# 10_RK3588_VCCIO1_VCCIO3_SARADC.net
KiCad netlist of a schematic drawn in Altium Designer
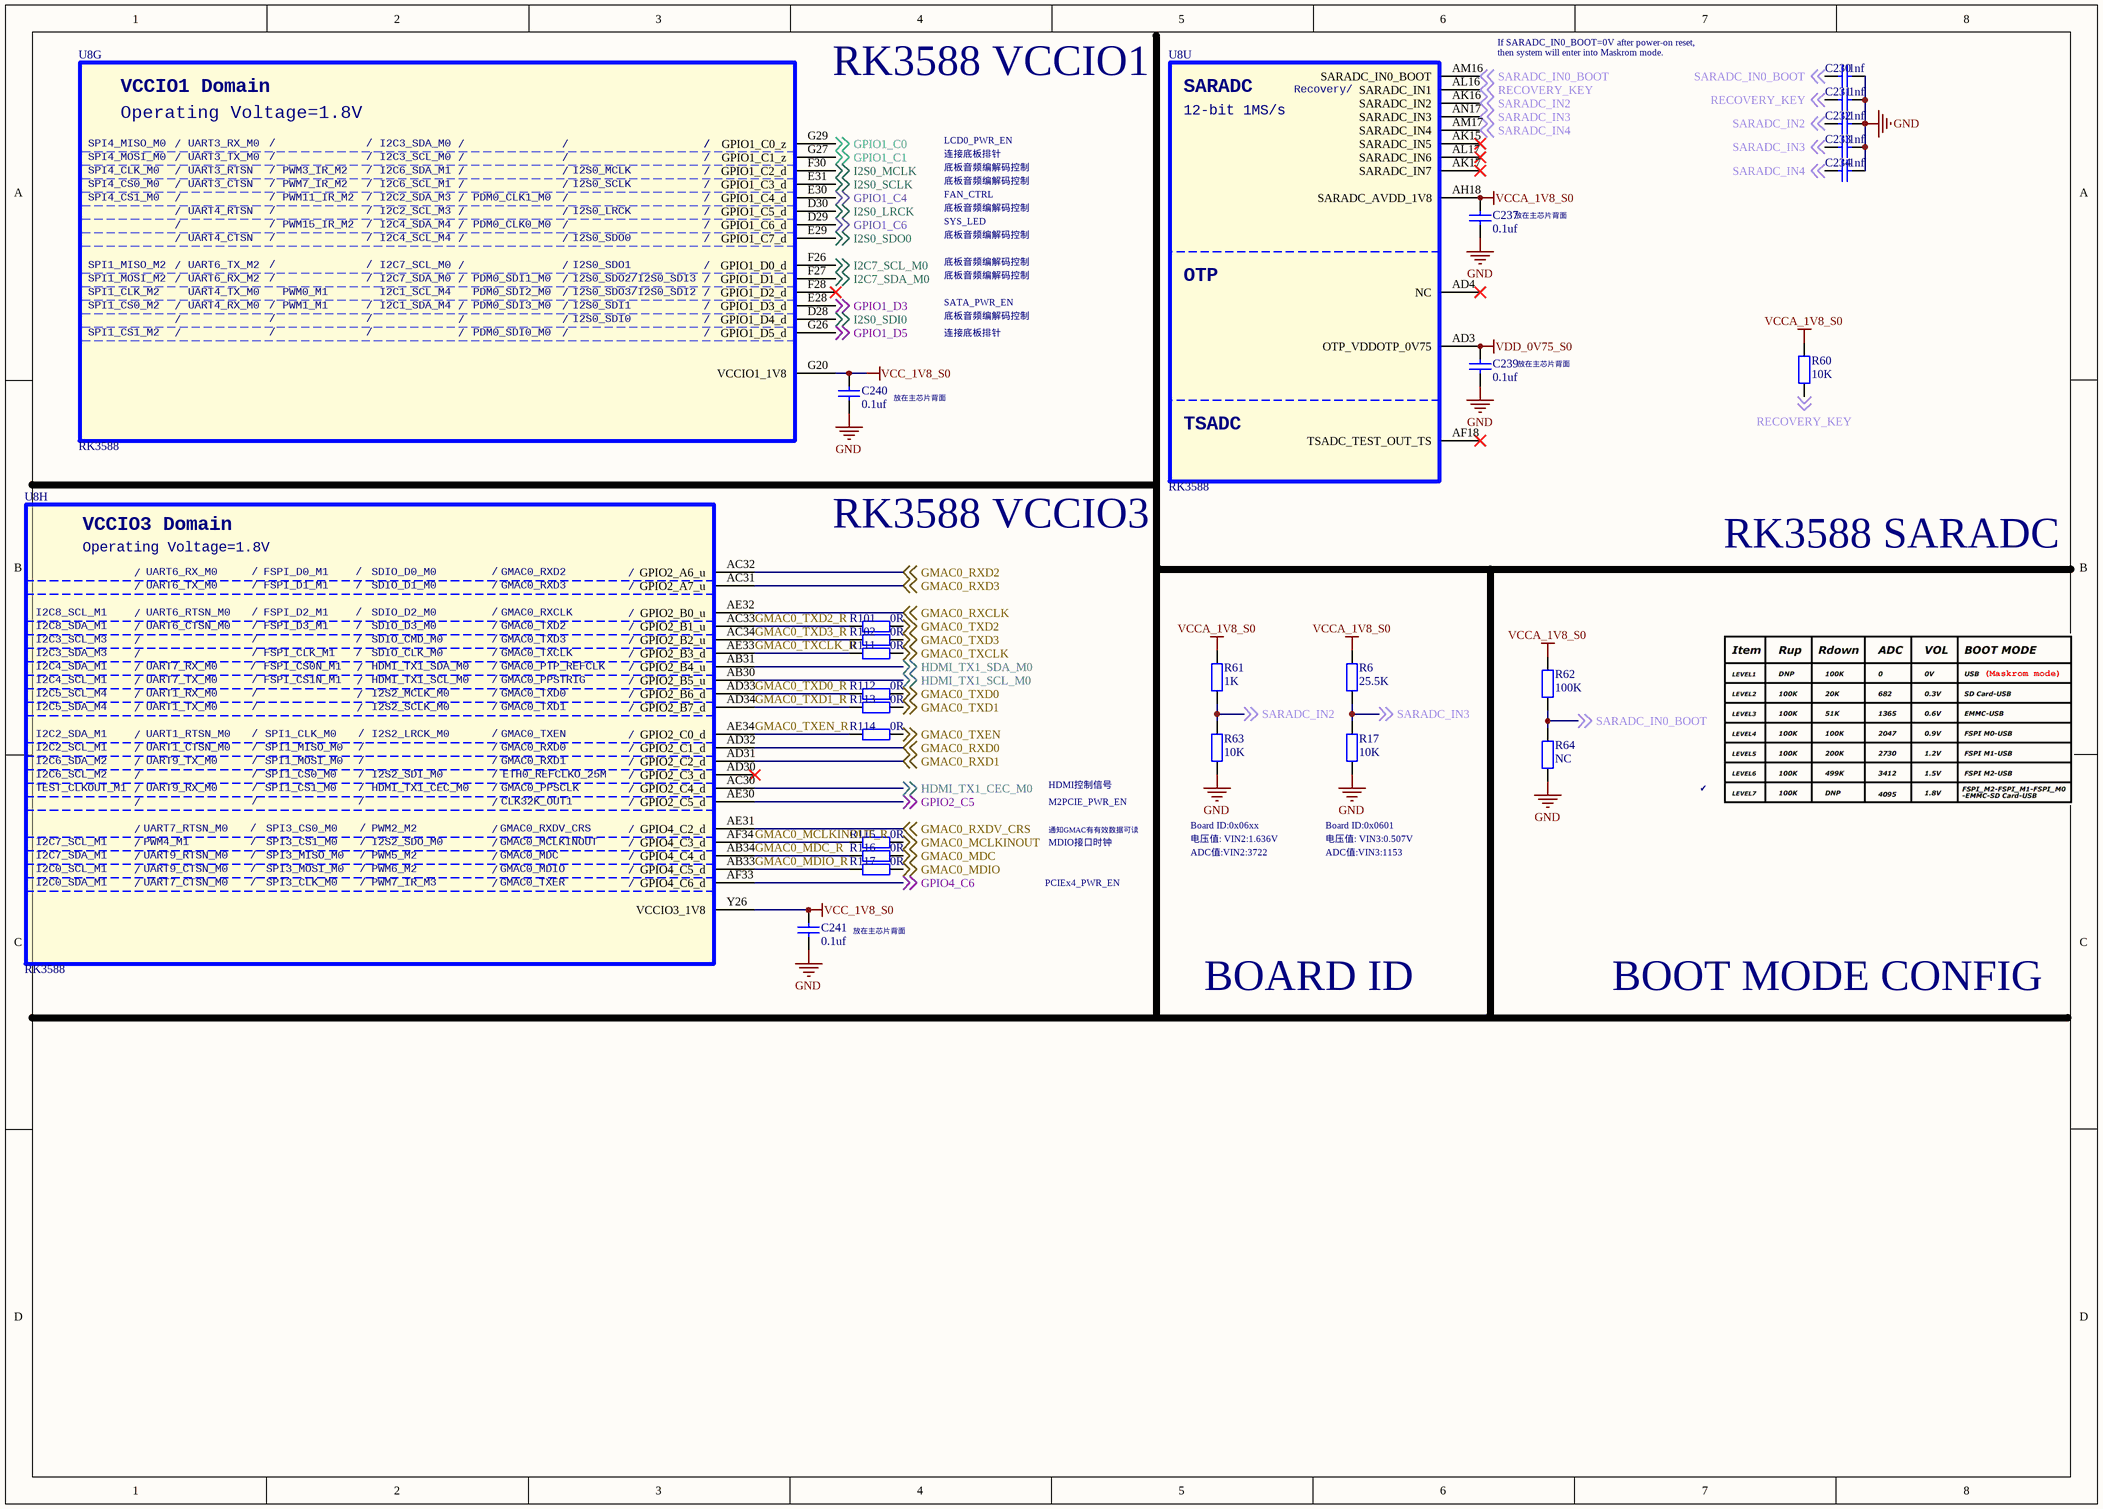
[diagram p0: 10.RK3588_VCCIO1_VCCIO3_SARADC.SchDoc]

(export (version "E")
  (design (tool "Eeschema 10.0.6"))
  (components
    (comp (ref "C230")
      (value "1nf")
      (footprint "0.PCB1:C0201_L")
      (description "贴片电容/MLCC电容")
      (libsource (lib "RK3588") (part "C"))
    )
    (comp (ref "C231")
      (value "1nf")
      (footprint "0.PCB1:C0201_L")
      (description "贴片电容/MLCC电容")
      (libsource (lib "RK3588") (part "C"))
    )
    (comp (ref "C232")
      (value "1nf")
      (footprint "0.PCB1:C0201_L")
      (description "贴片电容/MLCC电容")
      (libsource (lib "RK3588") (part "C"))
    )
    (comp (ref "C233")
      (value "1nf")
      (footprint "0.PCB1:C0201_L")
      (description "贴片电容/MLCC电容")
      (libsource (lib "RK3588") (part "C"))
    )
    (comp (ref "C234")
      (value "1nf")
      (footprint "0.PCB1:C0201_L")
      (description "贴片电容/MLCC电容")
      (libsource (lib "RK3588") (part "C"))
    )
    (comp (ref "C237")
      (value "0.1uf")
      (footprint "0.PCB1:C0201_L")
      (description "贴片电容/MLCC电容")
      (libsource (lib "RK3588") (part "C"))
    )
    (comp (ref "C239")
      (value "0.1uf")
      (footprint "0.PCB1:C0201_L")
      (description "贴片电容/MLCC电容")
      (libsource (lib "RK3588") (part "C"))
    )
    (comp (ref "C240")
      (value "0.1uf")
      (footprint "0.PCB1:C0201_L")
      (description "贴片电容/MLCC电容")
      (libsource (lib "RK3588") (part "C"))
    )
    (comp (ref "C241")
      (value "0.1uf")
      (footprint "0.PCB1:C0201_L")
      (description "贴片电容/MLCC电容")
      (libsource (lib "RK3588") (part "C"))
    )
    (comp (ref "R6")
      (value "25.5K")
      (footprint "0.PCB1:R0402_L")
      (description "贴片电阻")
      (libsource (lib "RK3588") (part "R"))
    )
    (comp (ref "R17")
      (value "10K")
      (footprint "0.PCB1:R0402_L")
      (description "贴片电阻")
      (libsource (lib "RK3588") (part "R"))
    )
    (comp (ref "R60")
      (value "10K")
      (footprint "0.PCB1:R0402_L")
      (description "贴片电阻")
      (libsource (lib "RK3588") (part "R"))
    )
    (comp (ref "R61")
      (value "1K")
      (footprint "0.PCB1:R0402_L")
      (description "贴片电阻")
      (libsource (lib "RK3588") (part "R"))
    )
    (comp (ref "R62")
      (value "100K")
      (footprint "0.PCB1:R0402_L")
      (description "贴片电阻")
      (libsource (lib "RK3588") (part "R"))
    )
    (comp (ref "R63")
      (value "10K")
      (footprint "0.PCB1:R0402_L")
      (description "贴片电阻")
      (libsource (lib "RK3588") (part "R"))
    )
    (comp (ref "R64")
      (value "NC")
      (footprint "0.PCB1:R0402_L")
      (description "贴片电阻")
      (libsource (lib "RK3588") (part "R"))
    )
    (comp (ref "R101")
      (value "0R")
      (footprint "0.PCB1:R0201_L")
      (description "贴片电阻")
      (libsource (lib "RK3588") (part "R"))
    )
    (comp (ref "R102")
      (value "0R")
      (footprint "0.PCB1:R0201_L")
      (description "贴片电阻")
      (libsource (lib "RK3588") (part "R"))
    )
    (comp (ref "R111")
      (value "0R")
      (footprint "0.PCB1:R0201_L")
      (description "贴片电阻")
      (libsource (lib "RK3588") (part "R"))
    )
    (comp (ref "R112")
      (value "0R")
      (footprint "0.PCB1:R0201_L")
      (description "贴片电阻")
      (libsource (lib "RK3588") (part "R"))
    )
    (comp (ref "R113")
      (value "0R")
      (footprint "0.PCB1:R0201_L")
      (description "贴片电阻")
      (libsource (lib "RK3588") (part "R"))
    )
    (comp (ref "R114")
      (value "0R")
      (footprint "0.PCB1:R0201_L")
      (description "贴片电阻")
      (libsource (lib "RK3588") (part "R"))
    )
    (comp (ref "R115")
      (value "0R")
      (footprint "0.PCB1:R0201_L")
      (description "贴片电阻")
      (libsource (lib "RK3588") (part "R"))
    )
    (comp (ref "R116")
      (value "0R")
      (footprint "0.PCB1:R0201_L")
      (description "贴片电阻")
      (libsource (lib "RK3588") (part "R"))
    )
    (comp (ref "R117")
      (value "0R")
      (footprint "0.PCB1:R0201_L")
      (description "贴片电阻")
      (libsource (lib "RK3588") (part "R"))
    )
    (comp (ref "U8")
      (value "RK3588")
      (footprint "0.PCB1:BGA1088_23R00X23R00X2R00")
      (description "ROCKCHIP SOC")
      (libsource (lib "RK3588") (part "SOC_RK3588"))
    )
  )
  (nets
    (net (code "1") (name "/GMAC0_MCLKINOUT_R") (class "Default")
      (node (ref "R115") (pin "1") (pinfunction "1_1") (pintype "passive"))
      (node (ref "U8") (pin "AF34") (pinfunction "GPIO4_C3_d_AF34") (pintype "passive"))
    )
    (net (code "2") (name "/GMAC0_MDC_R") (class "Default")
      (node (ref "R116") (pin "1") (pinfunction "1_1") (pintype "passive"))
      (node (ref "U8") (pin "AB34") (pinfunction "GPIO4_C4_d_AB34") (pintype "passive"))
    )
    (net (code "3") (name "/GMAC0_MDIO_R") (class "Default")
      (node (ref "R117") (pin "1") (pinfunction "1_1") (pintype "passive"))
      (node (ref "U8") (pin "AB33") (pinfunction "GPIO4_C5_d_AB33") (pintype "passive"))
    )
    (net (code "4") (name "/GMAC0_TXCLK_R") (class "Default")
      (node (ref "R111") (pin "1") (pinfunction "1_1") (pintype "passive"))
      (node (ref "U8") (pin "AE33") (pinfunction "GPIO2_B3_d_AE33") (pintype "passive"))
    )
    (net (code "5") (name "/GMAC0_TXD0_R") (class "Default")
      (node (ref "R112") (pin "1") (pinfunction "1_1") (pintype "passive"))
      (node (ref "U8") (pin "AD33") (pinfunction "GPIO2_B6_d_AD33") (pintype "passive"))
    )
    (net (code "6") (name "/GMAC0_TXD1_R") (class "Default")
      (node (ref "R113") (pin "1") (pinfunction "1_1") (pintype "passive"))
      (node (ref "U8") (pin "AD34") (pinfunction "GPIO2_B7_d_AD34") (pintype "passive"))
    )
    (net (code "7") (name "/GMAC0_TXD2_R") (class "Default")
      (node (ref "R101") (pin "1") (pinfunction "1_1") (pintype "passive"))
      (node (ref "U8") (pin "AC33") (pinfunction "GPIO2_B1_u_AC33") (pintype "passive"))
    )
    (net (code "8") (name "/GMAC0_TXD3_R") (class "Default")
      (node (ref "R102") (pin "1") (pinfunction "1_1") (pintype "passive"))
      (node (ref "U8") (pin "AC34") (pinfunction "GPIO2_B2_u_AC34") (pintype "passive"))
    )
    (net (code "9") (name "/GMAC0_TXEN_R") (class "Default")
      (node (ref "R114") (pin "1") (pinfunction "1_1") (pintype "passive"))
      (node (ref "U8") (pin "AE34") (pinfunction "GPIO2_C0_d_AE34") (pintype "passive"))
    )
    (net (code "10") (name "GMAC0_MCLKINOUT") (class "Default")
      (node (ref "R115") (pin "2") (pinfunction "2_2") (pintype "passive"))
    )
    (net (code "11") (name "GMAC0_MDC") (class "Default")
      (node (ref "R116") (pin "2") (pinfunction "2_2") (pintype "passive"))
    )
    (net (code "12") (name "GMAC0_MDIO") (class "Default")
      (node (ref "R117") (pin "2") (pinfunction "2_2") (pintype "passive"))
    )
    (net (code "13") (name "GMAC0_RXCLK") (class "Default")
      (node (ref "U8") (pin "AE32") (pinfunction "GPIO2_B0_u_AE32") (pintype "passive"))
    )
    (net (code "14") (name "GMAC0_RXD0") (class "Default")
      (node (ref "U8") (pin "AD32") (pinfunction "GPIO2_C1_d_AD32") (pintype "passive"))
    )
    (net (code "15") (name "GMAC0_RXD1") (class "Default")
      (node (ref "U8") (pin "AD31") (pinfunction "GPIO2_C2_d_AD31") (pintype "passive"))
    )
    (net (code "16") (name "GMAC0_RXD2") (class "Default")
      (node (ref "U8") (pin "AC32") (pinfunction "GPIO2_A6_u_AC32") (pintype "passive"))
    )
    (net (code "17") (name "GMAC0_RXD3") (class "Default")
      (node (ref "U8") (pin "AC31") (pinfunction "GPIO2_A7_u_AC31") (pintype "passive"))
    )
    (net (code "18") (name "GMAC0_RXDV_CRS") (class "Default")
      (node (ref "U8") (pin "AE31") (pinfunction "GPIO4_C2_d_AE31") (pintype "passive"))
    )
    (net (code "19") (name "GMAC0_TXCLK") (class "Default")
      (node (ref "R111") (pin "2") (pinfunction "2_2") (pintype "passive"))
    )
    (net (code "20") (name "GMAC0_TXD0") (class "Default")
      (node (ref "R112") (pin "2") (pinfunction "2_2") (pintype "passive"))
    )
    (net (code "21") (name "GMAC0_TXD1") (class "Default")
      (node (ref "R113") (pin "2") (pinfunction "2_2") (pintype "passive"))
    )
    (net (code "22") (name "GMAC0_TXD2") (class "Default")
      (node (ref "R101") (pin "2") (pinfunction "2_2") (pintype "passive"))
    )
    (net (code "23") (name "GMAC0_TXD3") (class "Default")
      (node (ref "R102") (pin "2") (pinfunction "2_2") (pintype "passive"))
    )
    (net (code "24") (name "GMAC0_TXEN") (class "Default")
      (node (ref "R114") (pin "2") (pinfunction "2_2") (pintype "passive"))
    )
    (net (code "25") (name "GND") (class "Default")
      (node (ref "C230") (pin "2") (pinfunction "2_2") (pintype "passive"))
      (node (ref "C231") (pin "2") (pinfunction "2_2") (pintype "passive"))
      (node (ref "C232") (pin "2") (pinfunction "2_2") (pintype "passive"))
      (node (ref "C233") (pin "2") (pinfunction "2_2") (pintype "passive"))
      (node (ref "C234") (pin "2") (pinfunction "2_2") (pintype "passive"))
      (node (ref "C237") (pin "1") (pinfunction "1_1") (pintype "passive"))
      (node (ref "C239") (pin "1") (pinfunction "1_1") (pintype "passive"))
      (node (ref "C240") (pin "1") (pinfunction "1_1") (pintype "passive"))
      (node (ref "C241") (pin "1") (pinfunction "1_1") (pintype "passive"))
      (node (ref "R17") (pin "1") (pinfunction "1_1") (pintype "passive"))
      (node (ref "R63") (pin "1") (pinfunction "1_1") (pintype "passive"))
      (node (ref "R64") (pin "1") (pinfunction "1_1") (pintype "passive"))
    )
    (net (code "26") (name "GPIO1_C0") (class "Default")
      (node (ref "U8") (pin "G29") (pinfunction "GPIO1_C0_z_G29") (pintype "passive"))
    )
    (net (code "27") (name "GPIO1_C1") (class "Default")
      (node (ref "U8") (pin "G27") (pinfunction "GPIO1_C1_z_G27") (pintype "passive"))
    )
    (net (code "28") (name "GPIO1_C4") (class "Default")
      (node (ref "U8") (pin "E30") (pinfunction "GPIO1_C4_d_E30") (pintype "passive"))
    )
    (net (code "29") (name "GPIO1_C6") (class "Default")
      (node (ref "U8") (pin "D29") (pinfunction "GPIO1_C6_d_D29") (pintype "passive"))
    )
    (net (code "30") (name "GPIO1_D3") (class "Default")
      (node (ref "U8") (pin "E28") (pinfunction "GPIO1_D3_d_E28") (pintype "passive"))
    )
    (net (code "31") (name "GPIO1_D5") (class "Default")
      (node (ref "U8") (pin "G26") (pinfunction "GPIO1_D5_d_G26") (pintype "passive"))
    )
    (net (code "32") (name "GPIO2_C5") (class "Default")
      (node (ref "U8") (pin "AE30") (pinfunction "GPIO2_C5_d_AE30") (pintype "passive"))
    )
    (net (code "33") (name "GPIO4_C6") (class "Default")
      (node (ref "U8") (pin "AF33") (pinfunction "GPIO4_C6_d_AF33") (pintype "passive"))
    )
    (net (code "34") (name "HDMI_TX1_CEC_M0") (class "Default")
      (node (ref "U8") (pin "AC30") (pinfunction "GPIO2_C4_d_AC30") (pintype "passive"))
    )
    (net (code "35") (name "HDMI_TX1_SCL_M0") (class "Default")
      (node (ref "U8") (pin "AB30") (pinfunction "GPIO2_B5_u_AB30") (pintype "passive"))
    )
    (net (code "36") (name "HDMI_TX1_SDA_M0") (class "Default")
      (node (ref "U8") (pin "AB31") (pinfunction "GPIO2_B4_u_AB31") (pintype "passive"))
    )
    (net (code "37") (name "I2C7_SCL_M0") (class "Default")
      (node (ref "U8") (pin "F26") (pinfunction "GPIO1_D0_d_F26") (pintype "passive"))
    )
    (net (code "38") (name "I2C7_SDA_M0") (class "Default")
      (node (ref "U8") (pin "F27") (pinfunction "GPIO1_D1_d_F27") (pintype "passive"))
    )
    (net (code "39") (name "I2S0_LRCK") (class "Default")
      (node (ref "U8") (pin "D30") (pinfunction "GPIO1_C5_d_D30") (pintype "passive"))
    )
    (net (code "40") (name "I2S0_MCLK") (class "Default")
      (node (ref "U8") (pin "F30") (pinfunction "GPIO1_C2_d_F30") (pintype "passive"))
    )
    (net (code "41") (name "I2S0_SCLK") (class "Default")
      (node (ref "U8") (pin "E31") (pinfunction "GPIO1_C3_d_E31") (pintype "passive"))
    )
    (net (code "42") (name "I2S0_SDI0") (class "Default")
      (node (ref "U8") (pin "D28") (pinfunction "GPIO1_D4_d_D28") (pintype "passive"))
    )
    (net (code "43") (name "I2S0_SDO0") (class "Default")
      (node (ref "U8") (pin "E29") (pinfunction "GPIO1_C7_d_E29") (pintype "passive"))
    )
    (net (code "44") (name "RECOVERY_KEY") (class "Default")
      (node (ref "C231") (pin "1") (pinfunction "1_1") (pintype "passive"))
      (node (ref "R60") (pin "1") (pinfunction "1_1") (pintype "passive"))
      (node (ref "U8") (pin "AL16") (pinfunction "SARADC_IN1_AL16") (pintype "passive"))
    )
    (net (code "45") (name "SARADC_IN0_BOOT") (class "Default")
      (node (ref "C230") (pin "1") (pinfunction "1_1") (pintype "passive"))
      (node (ref "R62") (pin "1") (pinfunction "1_1") (pintype "passive"))
      (node (ref "R64") (pin "2") (pinfunction "2_2") (pintype "passive"))
      (node (ref "U8") (pin "AM16") (pinfunction "SARADC_IN0_BOOT_AM16") (pintype "passive"))
    )
    (net (code "46") (name "SARADC_IN2") (class "Default")
      (node (ref "C232") (pin "1") (pinfunction "1_1") (pintype "passive"))
      (node (ref "R61") (pin "1") (pinfunction "1_1") (pintype "passive"))
      (node (ref "R63") (pin "2") (pinfunction "2_2") (pintype "passive"))
      (node (ref "U8") (pin "AK16") (pinfunction "SARADC_IN2_AK16") (pintype "passive"))
    )
    (net (code "47") (name "SARADC_IN3") (class "Default")
      (node (ref "C233") (pin "1") (pinfunction "1_1") (pintype "passive"))
      (node (ref "R17") (pin "2") (pinfunction "2_2") (pintype "passive"))
      (node (ref "R6") (pin "1") (pinfunction "1_1") (pintype "passive"))
      (node (ref "U8") (pin "AN17") (pinfunction "SARADC_IN3_AN17") (pintype "passive"))
    )
    (net (code "48") (name "SARADC_IN4") (class "Default")
      (node (ref "C234") (pin "1") (pinfunction "1_1") (pintype "passive"))
      (node (ref "U8") (pin "AM17") (pinfunction "SARADC_IN4_AM17") (pintype "passive"))
    )
    (net (code "49") (name "VCCA_1V8_S0") (class "Default")
      (node (ref "C237") (pin "2") (pinfunction "2_2") (pintype "passive"))
      (node (ref "R6") (pin "2") (pinfunction "2_2") (pintype "passive"))
      (node (ref "R60") (pin "2") (pinfunction "2_2") (pintype "passive"))
      (node (ref "R61") (pin "2") (pinfunction "2_2") (pintype "passive"))
      (node (ref "R62") (pin "2") (pinfunction "2_2") (pintype "passive"))
      (node (ref "U8") (pin "AH18") (pinfunction "SARADC_AVDD_1V8_AH18") (pintype "power_in"))
    )
    (net (code "50") (name "VCC_1V8_S0") (class "Default")
      (node (ref "C240") (pin "2") (pinfunction "2_2") (pintype "passive"))
      (node (ref "C241") (pin "2") (pinfunction "2_2") (pintype "passive"))
      (node (ref "U8") (pin "G20") (pinfunction "VCCIO1_1V8_G20") (pintype "passive"))
      (node (ref "U8") (pin "Y26") (pinfunction "VCCIO3_1V8_Y26") (pintype "passive"))
    )
    (net (code "51") (name "VDD_0V75_S0") (class "Default")
      (node (ref "C239") (pin "2") (pinfunction "2_2") (pintype "passive"))
      (node (ref "U8") (pin "AD3") (pinfunction "OTP_VDDOTP_0V75_AD3") (pintype "passive"))
    )
    (net (code "52") (name "unconnected-(U8G-GPIO1_D2_d-PadF28)") (class "Default")
      (node (ref "U8") (pin "F28") (pinfunction "GPIO1_D2_d_F28") (pintype "passive+no_connect"))
    )
    (net (code "53") (name "unconnected-(U8H-GPIO2_C3_d-PadAD30)") (class "Default")
      (node (ref "U8") (pin "AD30") (pinfunction "GPIO2_C3_d_AD30") (pintype "passive+no_connect"))
    )
    (net (code "54") (name "unconnected-(U8U-NC-PadAD4)") (class "Default")
      (node (ref "U8") (pin "AD4") (pinfunction "NC_AD4") (pintype "passive+no_connect"))
    )
    (net (code "55") (name "unconnected-(U8U-SARADC_IN5-PadAK15)") (class "Default")
      (node (ref "U8") (pin "AK15") (pinfunction "SARADC_IN5_AK15") (pintype "passive+no_connect"))
    )
    (net (code "56") (name "unconnected-(U8U-SARADC_IN6-PadAL17)") (class "Default")
      (node (ref "U8") (pin "AL17") (pinfunction "SARADC_IN6_AL17") (pintype "passive+no_connect"))
    )
    (net (code "57") (name "unconnected-(U8U-SARADC_IN7-PadAK17)") (class "Default")
      (node (ref "U8") (pin "AK17") (pinfunction "SARADC_IN7_AK17") (pintype "passive+no_connect"))
    )
    (net (code "58") (name "unconnected-(U8U-TSADC_TEST_OUT_TS-PadAF18)") (class "Default")
      (node (ref "U8") (pin "AF18") (pinfunction "TSADC_TEST_OUT_TS_AF18") (pintype "passive+no_connect"))
    )
  )
)
